# stern-dreieck-anlauf.net
KiCad netlist of a schematic drawn in EAGLE
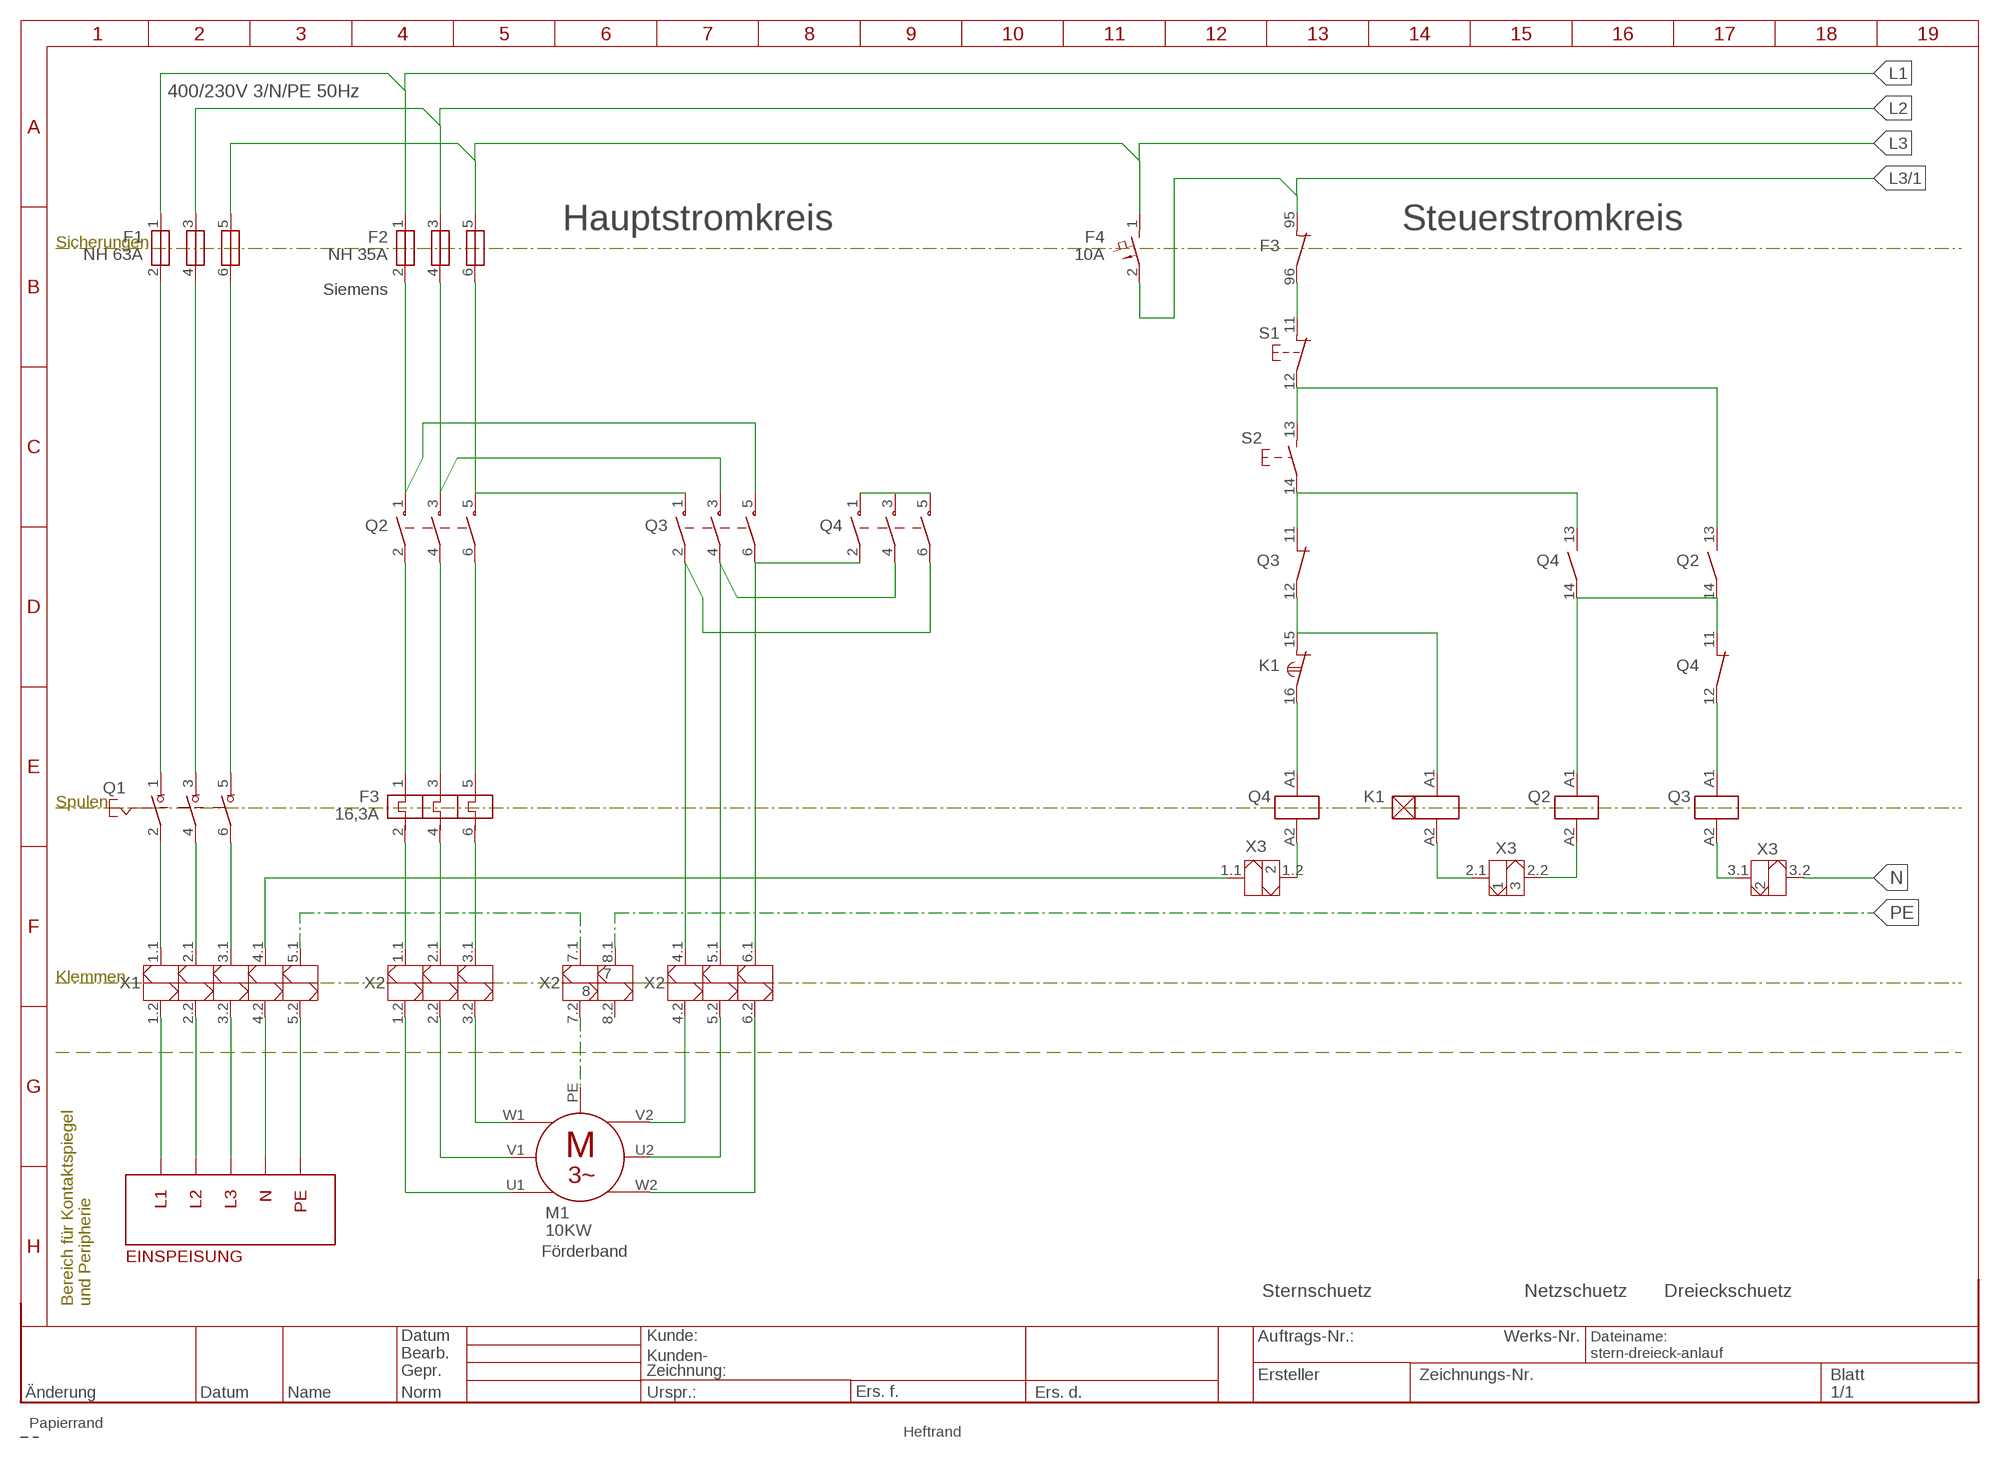
[diagram p0: schematic, sheet 1]

(export (version "E")
  (design (tool "Eeschema 10.0.6"))
  (components
    (comp (ref "F1")
      (value "NH 63A")
      (footprint "eagle-import:SICHERUNG_3-POL")
      (libsource (lib "eagle-import") (part "SICHERUNG_3-POL"))
    )
    (comp (ref "F2")
      (value "NH 35A")
      (footprint "eagle-import:SICHERUNG_3-POL")
      (fields (field (name "HERSTELLER") "Siemens"))
      (libsource (lib "eagle-import") (part "SICHERUNG_3-POL"))
    )
    (comp (ref "F3")
      (value "16,3A")
      (footprint "eagle-import:MOTORSCHUTZSCHALTER_3-POL_THERM_AUSLOESUNG_HILFSKONTAKT_95_96_97_98")
      (libsource (lib "eagle-import") (part "MOTORSCHUTZSCHALTER_3-POL_THERM_AUSLOESUNG_HILFSKONTAKTE"))
    )
    (comp (ref "F4")
      (value "10A")
      (footprint "eagle-import:LEITUNGSSCHUTZSCHALTER")
      (libsource (lib "eagle-import") (part "LEITUNGSSCHUTZSCHALTER"))
    )
    (comp (ref "K1")
      (value "HILFSSCHUETZ_OEFFNET_VERZOEGERT_15-16")
      (footprint "eagle-import:HILFSSCHUETZ_OEFFNET_VERZOEGERT_15-16")
      (libsource (lib "eagle-import") (part "HILFSSCHUETZ_OEFFNET_VERZOEGERT_15-16"))
    )
    (comp (ref "M1")
      (value "10KW")
      (footprint "eagle-import:MOTOR_3-PHASEN_STERN-DREIECK-ANLAUF.ALTERNATIV")
      (fields (field (name "FUNKTION") "Förderband"))
      (libsource (lib "eagle-import") (part "MOTOR_3-PHASEN_STERN-DREIECK-ANLAUF.ALTERNATIV"))
    )
    (comp (ref "Q1")
      (value "LASTTRENNSCHALTER_3-POL")
      (footprint "eagle-import:LASTTRENNSCHALTER_3-POL")
      (libsource (lib "eagle-import") (part "LASTTRENNSCHALTER_3-POL"))
    )
    (comp (ref "Q2")
      (value "HAUPTSCHUETZ_3-POL_HILFSKONTAKT_13-14")
      (footprint "eagle-import:HAUPTSCHUETZ_3-POL+HILFSKONTAKT_13-14")
      (libsource (lib "eagle-import") (part "HAUPTSCHUETZ_3-POL_HILFSKONTAKT_13-14"))
    )
    (comp (ref "Q3")
      (value "HAUPTSCHUETZ_3-POL_HILFSKONTAKT_11-12")
      (footprint "eagle-import:HAUPTSCHUETZ_3-POL+HILFSKONTAKT_11-12")
      (libsource (lib "eagle-import") (part "HAUPTSCHUETZ_3-POL_HILFSKONTAKT_11-12"))
    )
    (comp (ref "Q4")
      (value "HAUPTSCHUETZ_3-POL_HILFSKONTAKT_11-12_13-14")
      (footprint "eagle-import:HAUPTSCHUETZ_3-POL+HILFSKONTAKT_12-12_13-14")
      (libsource (lib "eagle-import") (part "HAUPTSCHUETZ_3-POL_HILFSKONTAKT_11-12_13-14"))
    )
    (comp (ref "S1")
      (value "TASTER_OEFFNER")
      (footprint "eagle-import:AUSTASTER")
      (libsource (lib "eagle-import") (part "TASTER_OEFFNER"))
    )
    (comp (ref "S2")
      (value "EINTASTER")
      (footprint "eagle-import:EINTASTER")
      (libsource (lib "eagle-import") (part "EINTASTER"))
    )
    (comp (ref "X1")
      (value "KLEMME-2_6-BRUECKE")
      (footprint "eagle-import:KLEMME-2_6-BRUECKE")
      (libsource (lib "eagle-import") (part "KLEMME-2_6-BRUECKE"))
    )
    (comp (ref "X2")
      (value "KLEMME-2_10-BRUECKE")
      (footprint "eagle-import:KLEMME-2_10-BRUECKE")
      (fields (field (name "72") "8") (field (name "81") "7"))
      (libsource (lib "eagle-import") (part "KLEMME-2_10-BRUECKE"))
    )
    (comp (ref "X3")
      (value "KLEMME-2_6-BRUECKE")
      (footprint "eagle-import:KLEMME-2_6-BRUECKE")
      (fields
        (field (name "12") "2")
        (field (name "21") "1")
        (field (name "22") "3")
        (field (name "31") "2")
        (field (name "NACH2") "v22")
      )
      (libsource (lib "eagle-import") (part "KLEMME-2_6-BRUECKE"))
    )
  )
  (nets
    (net (code "1") (name "L1") (class "Default")
      (node (ref "F1") (pin "1") (pinfunction "1_1") (pintype "passive"))
      (node (ref "F2") (pin "1") (pinfunction "1_1") (pintype "passive"))
    )
    (net (code "2") (name "L2") (class "Default")
      (node (ref "F1") (pin "3") (pinfunction "3_3") (pintype "passive"))
      (node (ref "F2") (pin "3") (pinfunction "3_3") (pintype "passive"))
    )
    (net (code "3") (name "L3") (class "Default")
      (node (ref "F1") (pin "5") (pinfunction "5_5") (pintype "passive"))
      (node (ref "F2") (pin "5") (pinfunction "5_5") (pintype "passive"))
      (node (ref "F4") (pin "1") (pinfunction "1_1") (pintype "passive"))
    )
    (net (code "4") (name "L3{slash}1") (class "Default")
      (node (ref "F3") (pin "95") (pinfunction "95_95") (pintype "passive"))
      (node (ref "F4") (pin "2") (pinfunction "2_2") (pintype "passive"))
    )
    (net (code "5") (name "N") (class "Default")
      (node (ref "X3") (pin "3.2") (pinfunction "2_3.2") (pintype "passive"))
    )
    (net (code "6") (name "Net-(F1-Pad2)") (class "Default")
      (node (ref "F1") (pin "2") (pinfunction "2_2") (pintype "passive"))
      (node (ref "Q1") (pin "1") (pinfunction "1_1") (pintype "input"))
    )
    (net (code "7") (name "Net-(F1-Pad4)") (class "Default")
      (node (ref "F1") (pin "4") (pinfunction "4_4") (pintype "passive"))
      (node (ref "Q1") (pin "3") (pinfunction "3_3") (pintype "input"))
    )
    (net (code "8") (name "Net-(F1-Pad6)") (class "Default")
      (node (ref "F1") (pin "6") (pinfunction "6_6") (pintype "passive"))
      (node (ref "Q1") (pin "5") (pinfunction "5_5") (pintype "input"))
    )
    (net (code "9") (name "Net-(F2-Pad2)") (class "Default")
      (node (ref "F2") (pin "2") (pinfunction "2_2") (pintype "passive"))
      (node (ref "Q2") (pin "1") (pinfunction "1_1") (pintype "passive"))
      (node (ref "Q3") (pin "5") (pinfunction "5_5") (pintype "passive"))
    )
    (net (code "10") (name "Net-(F2-Pad4)") (class "Default")
      (node (ref "F2") (pin "4") (pinfunction "4_4") (pintype "passive"))
      (node (ref "Q2") (pin "3") (pinfunction "3_3") (pintype "passive"))
      (node (ref "Q3") (pin "3") (pinfunction "3_3") (pintype "passive"))
    )
    (net (code "11") (name "Net-(F2-Pad6)") (class "Default")
      (node (ref "F2") (pin "6") (pinfunction "6_6") (pintype "passive"))
      (node (ref "Q2") (pin "5") (pinfunction "5_5") (pintype "passive"))
      (node (ref "Q3") (pin "1") (pinfunction "1_1") (pintype "passive"))
    )
    (net (code "12") (name "Net-(F3-Pad1)") (class "Default")
      (node (ref "F3") (pin "1") (pinfunction "1_1") (pintype "passive"))
      (node (ref "Q2") (pin "2") (pinfunction "2_2") (pintype "passive"))
    )
    (net (code "13") (name "Net-(F3-Pad3)") (class "Default")
      (node (ref "F3") (pin "3") (pinfunction "3_3") (pintype "passive"))
      (node (ref "Q2") (pin "4") (pinfunction "4_4") (pintype "passive"))
    )
    (net (code "14") (name "Net-(F3-Pad5)") (class "Default")
      (node (ref "F3") (pin "5") (pinfunction "5_5") (pintype "passive"))
      (node (ref "Q2") (pin "6") (pinfunction "6_6") (pintype "passive"))
    )
    (net (code "15") (name "Net-(K1B-5)") (class "Default")
      (node (ref "K1") (pin "15") (pinfunction "5_15") (pintype "passive"))
      (node (ref "K1") (pin "A1") (pinfunction "A1_A1") (pintype "passive"))
      (node (ref "Q3") (pin "12") (pinfunction "2_12") (pintype "passive"))
    )
    (net (code "16") (name "Net-(K1B-6)") (class "Default")
      (node (ref "K1") (pin "16") (pinfunction "6_16") (pintype "passive"))
      (node (ref "Q4") (pin "A1") (pinfunction "A1_A1") (pintype "input"))
    )
    (net (code "17") (name "Net-(Q2B-3)") (class "Default")
      (node (ref "Q2") (pin "13") (pinfunction "3_13") (pintype "passive"))
      (node (ref "S1") (pin "12") (pinfunction "2_12") (pintype "passive"))
      (node (ref "S2") (pin "13") (pinfunction "S1_13") (pintype "passive"))
    )
    (net (code "18") (name "Net-(Q2B-4)") (class "Default")
      (node (ref "Q2") (pin "14") (pinfunction "4_14") (pintype "passive"))
      (node (ref "Q2") (pin "A1") (pinfunction "A1_A1") (pintype "input"))
      (node (ref "Q4") (pin "11") (pinfunction "1_11") (pintype "passive"))
      (node (ref "Q4") (pin "14") (pinfunction "4_14") (pintype "passive"))
    )
    (net (code "19") (name "Net-(Q3B-1)") (class "Default")
      (node (ref "Q3") (pin "11") (pinfunction "1_11") (pintype "passive"))
      (node (ref "Q4") (pin "13") (pinfunction "3_13") (pintype "passive"))
      (node (ref "S2") (pin "14") (pinfunction "CS1_14") (pintype "passive"))
    )
    (net (code "20") (name "Net-(Q4-Pad1)") (class "Default")
      (node (ref "Q4") (pin "1") (pinfunction "1_1") (pintype "passive"))
      (node (ref "Q4") (pin "3") (pinfunction "3_3") (pintype "passive"))
      (node (ref "Q4") (pin "5") (pinfunction "5_5") (pintype "passive"))
    )
    (net (code "21") (name "Net-(Q4C-2)") (class "Default")
      (node (ref "Q3") (pin "A1") (pinfunction "A1_A1") (pintype "input"))
      (node (ref "Q4") (pin "12") (pinfunction "2_12") (pintype "passive"))
    )
    (net (code "22") (name "Net-(S1-1)") (class "Default")
      (node (ref "F3") (pin "96") (pinfunction "96_96") (pintype "passive"))
      (node (ref "S1") (pin "11") (pinfunction "1_11") (pintype "passive"))
    )
    (net (code "23") (name "Net-(X1A-1)") (class "Default")
      (node (ref "Q1") (pin "2") (pinfunction "2_2") (pintype "input"))
      (node (ref "X1") (pin "1.1") (pinfunction "1_1.1") (pintype "passive"))
    )
    (net (code "24") (name "Net-(X1A-2)") (class "Default")
      (node (ref "X1") (pin "1.2") (pinfunction "2_1.2") (pintype "passive"))
    )
    (net (code "25") (name "Net-(X1B-1)") (class "Default")
      (node (ref "Q1") (pin "4") (pinfunction "4_4") (pintype "input"))
      (node (ref "X1") (pin "2.1") (pinfunction "1_2.1") (pintype "passive"))
    )
    (net (code "26") (name "Net-(X1B-2)") (class "Default")
      (node (ref "X1") (pin "2.2") (pinfunction "2_2.2") (pintype "passive"))
    )
    (net (code "27") (name "Net-(X1C-1)") (class "Default")
      (node (ref "Q1") (pin "6") (pinfunction "6_6") (pintype "input"))
      (node (ref "X1") (pin "3.1") (pinfunction "1_3.1") (pintype "passive"))
    )
    (net (code "28") (name "Net-(X1C-2)") (class "Default")
      (node (ref "X1") (pin "3.2") (pinfunction "2_3.2") (pintype "passive"))
    )
    (net (code "29") (name "Net-(X1D-1)") (class "Default")
      (node (ref "X1") (pin "4.1") (pinfunction "1_4.1") (pintype "passive"))
      (node (ref "X3") (pin "1.1") (pinfunction "1_1.1") (pintype "passive"))
    )
    (net (code "30") (name "Net-(X1D-2)") (class "Default")
      (node (ref "X1") (pin "4.2") (pinfunction "2_4.2") (pintype "passive"))
    )
    (net (code "31") (name "Net-(X1E-1)") (class "Default")
      (node (ref "X1") (pin "5.1") (pinfunction "1_5.1") (pintype "passive"))
      (node (ref "X2") (pin "7.1") (pinfunction "1_7.1") (pintype "passive"))
    )
    (net (code "32") (name "Net-(X1E-2)") (class "Default")
      (node (ref "X1") (pin "5.2") (pinfunction "2_5.2") (pintype "passive"))
    )
    (net (code "33") (name "Net-(X2A-1)") (class "Default")
      (node (ref "F3") (pin "2") (pinfunction "2_2") (pintype "passive"))
      (node (ref "X2") (pin "1.1") (pinfunction "1_1.1") (pintype "passive"))
    )
    (net (code "34") (name "Net-(X2A-2)") (class "Default")
      (node (ref "M1") (pin "U1") (pinfunction "U1_U1") (pintype "passive"))
      (node (ref "X2") (pin "1.2") (pinfunction "2_1.2") (pintype "passive"))
    )
    (net (code "35") (name "Net-(X2C-1)") (class "Default")
      (node (ref "F3") (pin "4") (pinfunction "4_4") (pintype "passive"))
      (node (ref "X2") (pin "2.1") (pinfunction "1_2.1") (pintype "passive"))
    )
    (net (code "36") (name "Net-(X2C-2)") (class "Default")
      (node (ref "M1") (pin "V1") (pinfunction "V1_V1") (pintype "passive"))
      (node (ref "X2") (pin "2.2") (pinfunction "2_2.2") (pintype "passive"))
    )
    (net (code "37") (name "Net-(X2D-1)") (class "Default")
      (node (ref "F3") (pin "6") (pinfunction "6_6") (pintype "passive"))
      (node (ref "X2") (pin "3.1") (pinfunction "1_3.1") (pintype "passive"))
    )
    (net (code "38") (name "Net-(X2D-2)") (class "Default")
      (node (ref "M1") (pin "W1") (pinfunction "W1_W1") (pintype "passive"))
      (node (ref "X2") (pin "3.2") (pinfunction "2_3.2") (pintype "passive"))
    )
    (net (code "39") (name "Net-(X2E-1)") (class "Default")
      (node (ref "Q3") (pin "2") (pinfunction "2_2") (pintype "passive"))
      (node (ref "Q4") (pin "6") (pinfunction "6_6") (pintype "passive"))
      (node (ref "X2") (pin "4.1") (pinfunction "1_4.1") (pintype "passive"))
    )
    (net (code "40") (name "Net-(X2E-2)") (class "Default")
      (node (ref "M1") (pin "V2") (pinfunction "V2_V2") (pintype "passive"))
      (node (ref "X2") (pin "4.2") (pinfunction "2_4.2") (pintype "passive"))
    )
    (net (code "41") (name "Net-(X2F-1)") (class "Default")
      (node (ref "Q3") (pin "4") (pinfunction "4_4") (pintype "passive"))
      (node (ref "Q4") (pin "4") (pinfunction "4_4") (pintype "passive"))
      (node (ref "X2") (pin "5.1") (pinfunction "1_5.1") (pintype "passive"))
    )
    (net (code "42") (name "Net-(X2F-2)") (class "Default")
      (node (ref "M1") (pin "U2") (pinfunction "U2_U2") (pintype "passive"))
      (node (ref "X2") (pin "5.2") (pinfunction "2_5.2") (pintype "passive"))
    )
    (net (code "43") (name "Net-(X2G-1)") (class "Default")
      (node (ref "Q3") (pin "6") (pinfunction "6_6") (pintype "passive"))
      (node (ref "Q4") (pin "2") (pinfunction "2_2") (pintype "passive"))
      (node (ref "X2") (pin "6.1") (pinfunction "1_6.1") (pintype "passive"))
    )
    (net (code "44") (name "Net-(X2G-2)") (class "Default")
      (node (ref "M1") (pin "W2") (pinfunction "W2_W2") (pintype "passive"))
      (node (ref "X2") (pin "6.2") (pinfunction "2_6.2") (pintype "passive"))
    )
    (net (code "45") (name "Net-(X2H-2)") (class "Default")
      (node (ref "M1") (pin "PE") (pinfunction "PE_PE") (pintype "passive"))
      (node (ref "X2") (pin "7.2") (pinfunction "2_7.2") (pintype "passive"))
    )
    (net (code "46") (name "Net-(X3A-2)") (class "Default")
      (node (ref "Q4") (pin "A2") (pinfunction "A2_A2") (pintype "input"))
      (node (ref "X3") (pin "1.2") (pinfunction "2_1.2") (pintype "passive"))
    )
    (net (code "47") (name "Net-(X3B-1)") (class "Default")
      (node (ref "K1") (pin "A2") (pinfunction "A2_A2") (pintype "passive"))
      (node (ref "X3") (pin "2.1") (pinfunction "1_2.1") (pintype "passive"))
    )
    (net (code "48") (name "Net-(X3B-2)") (class "Default")
      (node (ref "Q2") (pin "A2") (pinfunction "A2_A2") (pintype "input"))
      (node (ref "X3") (pin "2.2") (pinfunction "2_2.2") (pintype "passive"))
    )
    (net (code "49") (name "Net-(X3C-1)") (class "Default")
      (node (ref "Q3") (pin "A2") (pinfunction "A2_A2") (pintype "input"))
      (node (ref "X3") (pin "3.1") (pinfunction "1_3.1") (pintype "passive"))
    )
    (net (code "50") (name "PE") (class "Default")
      (node (ref "X2") (pin "8.1") (pinfunction "1_8.1") (pintype "passive"))
    )
    (net (code "51") (name "unconnected-(X2I-2-Pad8.2)") (class "Default")
      (node (ref "X2") (pin "8.2") (pinfunction "2_8.2") (pintype "passive"))
    )
  )
)
